# Sheet1.net
KiCad netlist of a schematic drawn in Altium Designer
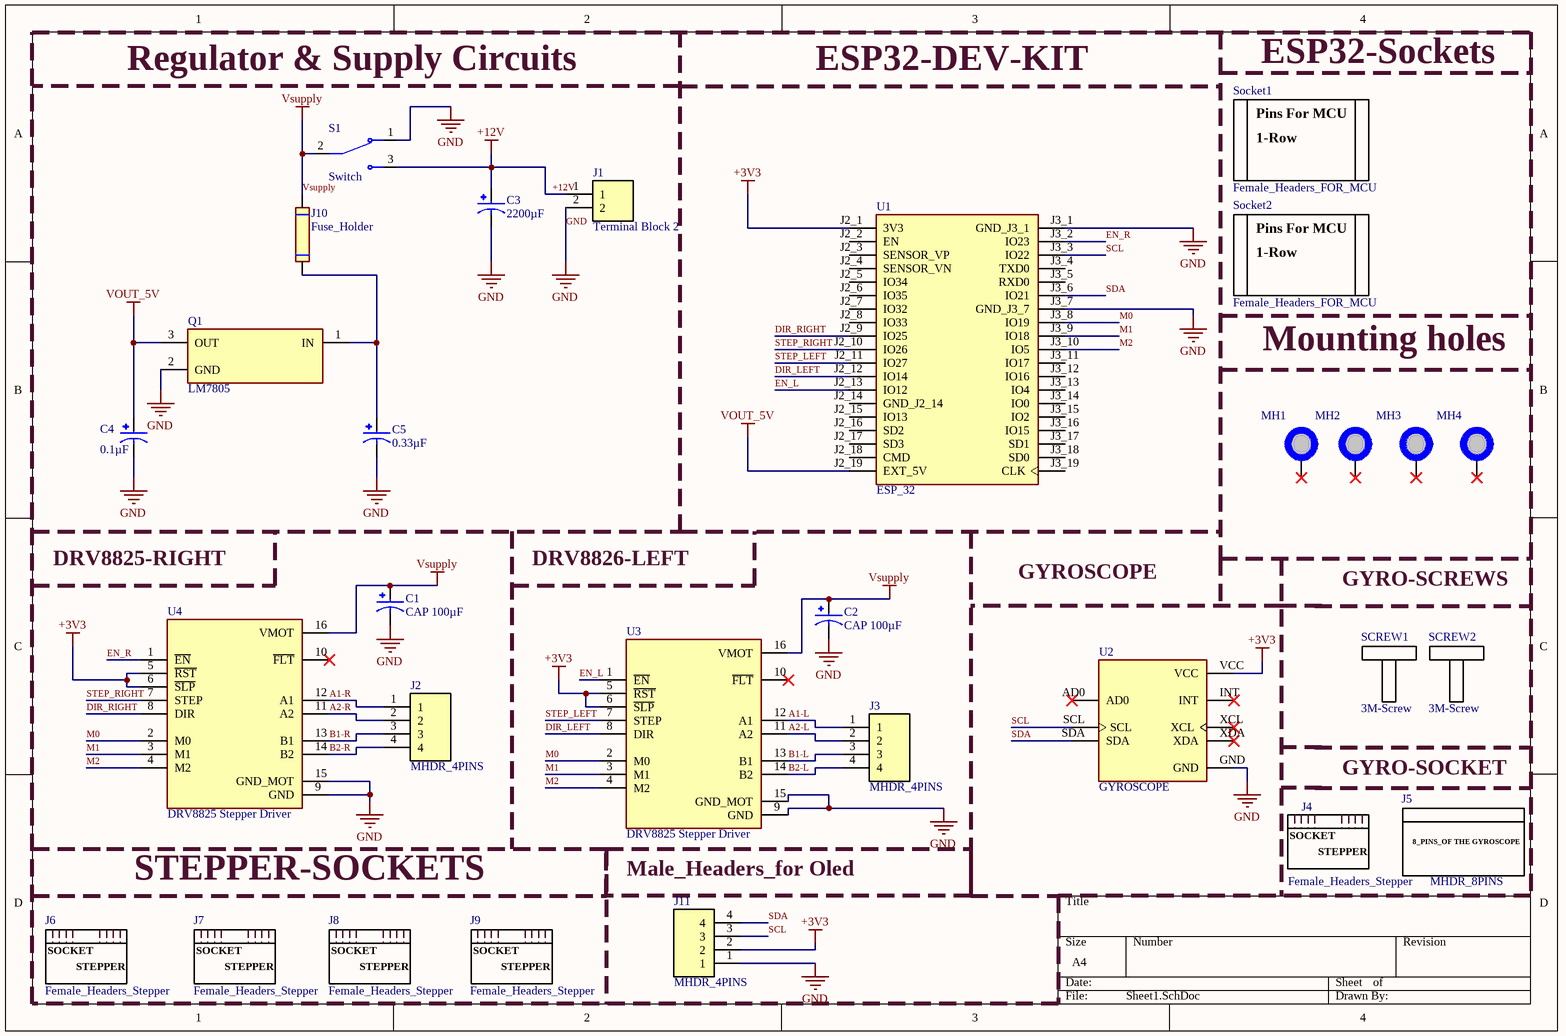
[diagram p0: Sheet1.SchDoc]

(export (version "E")
  (design (tool "Eeschema 10.0.6"))
  (components
    (comp (ref "C1") (value "CAP 100µF") (footprint "Cap_1µF") (libsource (lib "Schlib1") (part "CAP 100µF")))
    (comp (ref "C2") (value "CAP 100µF") (footprint "Cap_1µF") (libsource (lib "Schlib1") (part "CAP 100µF")))
    (comp (ref "C3")
      (value "2200µF")
      (footprint "CAP 2200UF")
      (libsource (lib "Schlib1") (part "CAP 2200µF"))
    )
    (comp (ref "C4") (value "0.1µF") (footprint "CAP 0.1UF") (libsource (lib "Schlib1") (part "CAP 0.1µF")))
    (comp (ref "C5") (value "0.33µF") (footprint "CAP 0.1UF") (libsource (lib "Schlib1") (part "CAP 0.33µF")))
    (comp (ref "J1")
      (value "Terminal Block 2")
      (footprint "Terminal Block 2")
      (libsource (lib "Schlib1") (part "Terminal Block 2"))
    )
    (comp (ref "J2") (value "MHDR_4PINS") (footprint "MHDR_4PINS") (libsource (lib "") (part "MHDR_4PINS_1")))
    (comp (ref "J3") (value "MHDR_4PINS") (footprint "MHDR_4PINS") (libsource (lib "") (part "MHDR_4PINS_1")))
    (comp (ref "J4")
      (value "Female_Headers_Stepper")
      (footprint "Female_STEPPER")
      (libsource (lib "Schlib1") (part "Female_Headers_Stepper"))
    )
    (comp (ref "J5")
      (value "MHDR_8PINS")
      (footprint "MHDR_8PINS")
      (libsource (lib "Schlib1") (part "MHDR_8PINS"))
    )
    (comp (ref "J6")
      (value "Female_Headers_Stepper")
      (footprint "Female_STEPPER")
      (libsource (lib "Schlib1") (part "Female_Headers_Stepper"))
    )
    (comp (ref "J7")
      (value "Female_Headers_Stepper")
      (footprint "Female_STEPPER")
      (libsource (lib "Schlib1") (part "Female_Headers_Stepper"))
    )
    (comp (ref "J8")
      (value "Female_Headers_Stepper")
      (footprint "Female_STEPPER")
      (libsource (lib "Schlib1") (part "Female_Headers_Stepper"))
    )
    (comp (ref "J9")
      (value "Female_Headers_Stepper")
      (footprint "Female_STEPPER")
      (libsource (lib "Schlib1") (part "Female_Headers_Stepper"))
    )
    (comp (ref "J10")
      (value "Fuse_Holder")
      (footprint "Fuse_Holder")
      (libsource (lib "Schlib1") (part "Fuse_Holder"))
    )
    (comp (ref "J11")
      (value "MHDR_4PINS")
      (footprint "MHDR_4PINS")
      (libsource (lib "Schlib1") (part "MHDR_4PINS"))
    )
    (comp (ref "MH1")
      (value "MH_7.4MMNC_3.2MMD (NO COPPER-NPTH)")
      (footprint "MH_7.4MMC_3.2MMD_NO_COPPER_NPTH")
      (libsource (lib "Schlib1") (part "MH_7.4MMNC_3.2MMD_1"))
    )
    (comp (ref "MH2")
      (value "MH_7.4MMNC_3.2MMD (NO COPPER-NPTH)")
      (footprint "MH_7.4MMC_3.2MMD_NO_COPPER_NPTH")
      (libsource (lib "Schlib1") (part "MH_7.4MMNC_3.2MMD_1"))
    )
    (comp (ref "MH3")
      (value "MH_7.4MMNC_3.2MMD (NO COPPER-NPTH)")
      (footprint "MH_7.4MMC_3.2MMD_NO_COPPER_NPTH")
      (libsource (lib "Schlib1") (part "MH_7.4MMNC_3.2MMD_1"))
    )
    (comp (ref "MH4")
      (value "MH_7.4MMNC_3.2MMD (NO COPPER-NPTH)")
      (footprint "MH_7.4MMC_3.2MMD_NO_COPPER_NPTH")
      (libsource (lib "Schlib1") (part "MH_7.4MMNC_3.2MMD_1"))
    )
    (comp (ref "Q1") (value "LM7805") (footprint "LM7805") (libsource (lib "Schlib1") (part "LM7805")))
    (comp (ref "S1") (value "Switch") (footprint "Switch") (libsource (lib "Schlib1") (part "Switch")))
    (comp (ref "SCREW1")
      (value "3M-Screw")
      (footprint "3M-SCREW")
      (libsource (lib "Schlib1") (part "3M-Screw"))
    )
    (comp (ref "SCREW2")
      (value "3M-Screw")
      (footprint "3M-SCREW")
      (libsource (lib "Schlib1") (part "3M-Screw"))
    )
    (comp (ref "Socket1")
      (value "Female_Headers_FOR_MCU")
      (footprint "Female_headers")
      (libsource (lib "Schlib1") (part "Female_Headers_FOR_MCU"))
    )
    (comp (ref "Socket2")
      (value "Female_Headers_FOR_MCU")
      (footprint "Female_headers")
      (libsource (lib "Schlib1") (part "Female_Headers_FOR_MCU"))
    )
    (comp (ref "U1") (value "ESP_32") (footprint "ESP_32") (libsource (lib "Schlib1") (part "ESP_32")))
    (comp (ref "U2")
      (value "GYROSCOPE")
      (footprint "GYROSCOPE")
      (libsource (lib "Schlib1") (part "GYROSCOPE"))
    )
    (comp (ref "U3")
      (value "DRV8825 Stepper Driver")
      (footprint "DRV8825 Stepper Driver")
      (libsource (lib "Schlib1") (part "DRV8825 Stepper Driver"))
    )
    (comp (ref "U4")
      (value "DRV8825 Stepper Driver")
      (footprint "DRV8825 Stepper Driver")
      (libsource (lib "Schlib1") (part "DRV8825 Stepper Driver"))
    )
  )
  (nets
    (net (code "1") (name "+3V3") (class "Default")
      (node (ref "J11") (pin "2") (pinfunction "2_2") (pintype "passive"))
      (node (ref "U1") (pin "J2_1") (pinfunction "3V3_J2_1") (pintype "passive"))
      (node (ref "U2") (pin "VCC") (pinfunction "VCC_VCC") (pintype "passive"))
      (node (ref "U3") (pin "5") (pinfunction "~{RST}_5") (pintype "passive"))
      (node (ref "U3") (pin "6") (pinfunction "~{SLP}_6") (pintype "passive"))
      (node (ref "U4") (pin "5") (pinfunction "~{RST}_5") (pintype "passive"))
      (node (ref "U4") (pin "6") (pinfunction "~{SLP}_6") (pintype "passive"))
    )
    (net (code "2") (name "+12V") (class "Default")
      (node (ref "C3") (pin "P") (pinfunction "P_P") (pintype "passive"))
      (node (ref "J1") (pin "1") (pinfunction "1_1") (pintype "passive"))
      (node (ref "S1") (pin "3") (pinfunction "3_3") (pintype "passive"))
    )
    (net (code "3") (name "/A1-L") (class "Default")
      (node (ref "J3") (pin "1") (pinfunction "1_1") (pintype "passive"))
      (node (ref "U3") (pin "12") (pinfunction "A1_12") (pintype "passive"))
    )
    (net (code "4") (name "/A1-R") (class "Default")
      (node (ref "J2") (pin "1") (pinfunction "1_1") (pintype "passive"))
      (node (ref "U4") (pin "12") (pinfunction "A1_12") (pintype "passive"))
    )
    (net (code "5") (name "/A2-L") (class "Default")
      (node (ref "J3") (pin "2") (pinfunction "2_2") (pintype "passive"))
      (node (ref "U3") (pin "11") (pinfunction "A2_11") (pintype "passive"))
    )
    (net (code "6") (name "/A2-R") (class "Default")
      (node (ref "J2") (pin "2") (pinfunction "2_2") (pintype "passive"))
      (node (ref "U4") (pin "11") (pinfunction "A2_11") (pintype "passive"))
    )
    (net (code "7") (name "/B1-L") (class "Default")
      (node (ref "J3") (pin "3") (pinfunction "3_3") (pintype "passive"))
      (node (ref "U3") (pin "13") (pinfunction "B1_13") (pintype "passive"))
    )
    (net (code "8") (name "/B1-R") (class "Default")
      (node (ref "J2") (pin "3") (pinfunction "3_3") (pintype "passive"))
      (node (ref "U4") (pin "13") (pinfunction "B1_13") (pintype "passive"))
    )
    (net (code "9") (name "/B2-L") (class "Default")
      (node (ref "J3") (pin "4") (pinfunction "4_4") (pintype "passive"))
      (node (ref "U3") (pin "14") (pinfunction "B2_14") (pintype "passive"))
    )
    (net (code "10") (name "/B2-R") (class "Default")
      (node (ref "J2") (pin "4") (pinfunction "4_4") (pintype "passive"))
      (node (ref "U4") (pin "14") (pinfunction "B2_14") (pintype "passive"))
    )
    (net (code "11") (name "/DIR_LEFT") (class "Default")
      (node (ref "U1") (pin "J2_12") (pinfunction "IO14_J2_12") (pintype "passive"))
      (node (ref "U3") (pin "8") (pinfunction "DIR_8") (pintype "passive"))
    )
    (net (code "12") (name "/DIR_RIGHT") (class "Default")
      (node (ref "U1") (pin "J2_9") (pinfunction "IO25_J2_9") (pintype "passive"))
      (node (ref "U4") (pin "8") (pinfunction "DIR_8") (pintype "passive"))
    )
    (net (code "13") (name "/EN_L") (class "Default")
      (node (ref "U1") (pin "J2_13") (pinfunction "IO12_J2_13") (pintype "passive"))
      (node (ref "U3") (pin "1") (pinfunction "~{EN}_1") (pintype "passive"))
    )
    (net (code "14") (name "/EN_R") (class "Default")
      (node (ref "U1") (pin "J3_2") (pinfunction "IO23_J3_2") (pintype "passive"))
      (node (ref "U4") (pin "1") (pinfunction "~{EN}_1") (pintype "passive"))
    )
    (net (code "15") (name "/M0") (class "Default")
      (node (ref "U1") (pin "J3_8") (pinfunction "IO19_J3_8") (pintype "passive"))
      (node (ref "U3") (pin "2") (pinfunction "M0_2") (pintype "passive"))
      (node (ref "U4") (pin "2") (pinfunction "M0_2") (pintype "passive"))
    )
    (net (code "16") (name "/M1") (class "Default")
      (node (ref "U1") (pin "J3_9") (pinfunction "IO18_J3_9") (pintype "passive"))
      (node (ref "U3") (pin "3") (pinfunction "M1_3") (pintype "passive"))
      (node (ref "U4") (pin "3") (pinfunction "M1_3") (pintype "passive"))
    )
    (net (code "17") (name "/M2") (class "Default")
      (node (ref "U1") (pin "J3_10") (pinfunction "IO5_J3_10") (pintype "passive"))
      (node (ref "U3") (pin "4") (pinfunction "M2_4") (pintype "passive"))
      (node (ref "U4") (pin "4") (pinfunction "M2_4") (pintype "passive"))
    )
    (net (code "18") (name "/SCL") (class "Default")
      (node (ref "J11") (pin "3") (pinfunction "3_3") (pintype "passive"))
      (node (ref "U1") (pin "J3_3") (pinfunction "IO22_J3_3") (pintype "passive"))
      (node (ref "U2") (pin "SCL") (pinfunction "SCL_SCL") (pintype "passive"))
    )
    (net (code "19") (name "/SDA") (class "Default")
      (node (ref "J11") (pin "4") (pinfunction "4_4") (pintype "passive"))
      (node (ref "U1") (pin "J3_6") (pinfunction "IO21_J3_6") (pintype "passive"))
      (node (ref "U2") (pin "SDA") (pinfunction "SDA_SDA") (pintype "passive"))
    )
    (net (code "20") (name "/STEP_LEFT") (class "Default")
      (node (ref "U1") (pin "J2_11") (pinfunction "IO27_J2_11") (pintype "passive"))
      (node (ref "U3") (pin "7") (pinfunction "STEP_7") (pintype "passive"))
    )
    (net (code "21") (name "/STEP_RIGHT") (class "Default")
      (node (ref "U1") (pin "J2_10") (pinfunction "IO26_J2_10") (pintype "passive"))
      (node (ref "U4") (pin "7") (pinfunction "STEP_7") (pintype "passive"))
    )
    (net (code "22") (name "GND") (class "Default")
      (node (ref "C1") (pin "N") (pinfunction "N_N") (pintype "passive"))
      (node (ref "C2") (pin "N") (pinfunction "N_N") (pintype "passive"))
      (node (ref "C3") (pin "N") (pinfunction "N_N") (pintype "passive"))
      (node (ref "C4") (pin "N") (pinfunction "N_N") (pintype "passive"))
      (node (ref "C5") (pin "N") (pinfunction "N_N") (pintype "passive"))
      (node (ref "J1") (pin "2") (pinfunction "2_2") (pintype "passive"))
      (node (ref "J11") (pin "1") (pinfunction "1_1") (pintype "passive"))
      (node (ref "Q1") (pin "2") (pinfunction "GND_2") (pintype "power_in"))
      (node (ref "S1") (pin "1") (pinfunction "1_1") (pintype "passive"))
      (node (ref "U1") (pin "J3_1") (pinfunction "GND_J3_1_J3_1") (pintype "passive"))
      (node (ref "U1") (pin "J3_7") (pinfunction "GND_J3_7_J3_7") (pintype "passive"))
      (node (ref "U2") (pin "GND") (pinfunction "GND_GND") (pintype "passive"))
      (node (ref "U3") (pin "15") (pinfunction "GND_MOT_15") (pintype "passive"))
      (node (ref "U3") (pin "9") (pinfunction "GND_9") (pintype "passive"))
      (node (ref "U4") (pin "15") (pinfunction "GND_MOT_15") (pintype "passive"))
      (node (ref "U4") (pin "9") (pinfunction "GND_9") (pintype "passive"))
    )
    (net (code "23") (name "Net-(Q1-IN)") (class "Default")
      (node (ref "C5") (pin "P") (pinfunction "P_P") (pintype "passive"))
      (node (ref "J10") (pin "1") (pinfunction "1_1") (pintype "passive"))
      (node (ref "Q1") (pin "1") (pinfunction "IN_1") (pintype "passive"))
    )
    (net (code "24") (name "VOUT_5V") (class "Default")
      (node (ref "C4") (pin "P") (pinfunction "P_P") (pintype "passive"))
      (node (ref "Q1") (pin "3") (pinfunction "OUT_3") (pintype "passive"))
      (node (ref "U1") (pin "J2_19") (pinfunction "EXT_5V_J2_19") (pintype "passive"))
    )
    (net (code "25") (name "Vsupply") (class "Default")
      (node (ref "C1") (pin "P") (pinfunction "P_P") (pintype "passive"))
      (node (ref "C2") (pin "P") (pinfunction "P_P") (pintype "passive"))
      (node (ref "J10") (pin "2") (pinfunction "2_2") (pintype "passive"))
      (node (ref "S1") (pin "2") (pinfunction "2_2") (pintype "passive"))
      (node (ref "U3") (pin "16") (pinfunction "VMOT_16") (pintype "passive"))
      (node (ref "U4") (pin "16") (pinfunction "VMOT_16") (pintype "passive"))
    )
    (net (code "26") (name "unconnected-(MH1-Pad1)") (class "Default")
      (node (ref "MH1") (pin "1") (pinfunction "1_1") (pintype "passive+no_connect"))
    )
    (net (code "27") (name "unconnected-(MH2-Pad1)") (class "Default")
      (node (ref "MH2") (pin "1") (pinfunction "1_1") (pintype "passive+no_connect"))
    )
    (net (code "28") (name "unconnected-(MH3-Pad1)") (class "Default")
      (node (ref "MH3") (pin "1") (pinfunction "1_1") (pintype "passive+no_connect"))
    )
    (net (code "29") (name "unconnected-(MH4-Pad1)") (class "Default")
      (node (ref "MH4") (pin "1") (pinfunction "1_1") (pintype "passive+no_connect"))
    )
    (net (code "30") (name "unconnected-(U1-CLK-PadJ3_19)") (class "Default")
      (node (ref "U1") (pin "J3_19") (pinfunction "CLK_J3_19") (pintype "passive"))
    )
    (net (code "31") (name "unconnected-(U1-CMD-PadJ2_18)") (class "Default")
      (node (ref "U1") (pin "J2_18") (pinfunction "CMD_J2_18") (pintype "passive"))
    )
    (net (code "32") (name "unconnected-(U1-EN-PadJ2_2)") (class "Default")
      (node (ref "U1") (pin "J2_2") (pinfunction "EN_J2_2") (pintype "passive"))
    )
    (net (code "33") (name "unconnected-(U1-GND_J2_14-PadJ2_14)") (class "Default")
      (node (ref "U1") (pin "J2_14") (pinfunction "GND_J2_14_J2_14") (pintype "passive"))
    )
    (net (code "34") (name "unconnected-(U1-IO0-PadJ3_14)") (class "Default")
      (node (ref "U1") (pin "J3_14") (pinfunction "IO0_J3_14") (pintype "passive"))
    )
    (net (code "35") (name "unconnected-(U1-IO2-PadJ3_15)") (class "Default")
      (node (ref "U1") (pin "J3_15") (pinfunction "IO2_J3_15") (pintype "passive"))
    )
    (net (code "36") (name "unconnected-(U1-IO4-PadJ3_13)") (class "Default")
      (node (ref "U1") (pin "J3_13") (pinfunction "IO4_J3_13") (pintype "passive"))
    )
    (net (code "37") (name "unconnected-(U1-IO13-PadJ2_15)") (class "Default")
      (node (ref "U1") (pin "J2_15") (pinfunction "IO13_J2_15") (pintype "passive"))
    )
    (net (code "38") (name "unconnected-(U1-IO15-PadJ3_16)") (class "Default")
      (node (ref "U1") (pin "J3_16") (pinfunction "IO15_J3_16") (pintype "passive"))
    )
    (net (code "39") (name "unconnected-(U1-IO16-PadJ3_12)") (class "Default")
      (node (ref "U1") (pin "J3_12") (pinfunction "IO16_J3_12") (pintype "passive"))
    )
    (net (code "40") (name "unconnected-(U1-IO17-PadJ3_11)") (class "Default")
      (node (ref "U1") (pin "J3_11") (pinfunction "IO17_J3_11") (pintype "passive"))
    )
    (net (code "41") (name "unconnected-(U1-IO32-PadJ2_7)") (class "Default")
      (node (ref "U1") (pin "J2_7") (pinfunction "IO32_J2_7") (pintype "passive"))
    )
    (net (code "42") (name "unconnected-(U1-IO33-PadJ2_8)") (class "Default")
      (node (ref "U1") (pin "J2_8") (pinfunction "IO33_J2_8") (pintype "passive"))
    )
    (net (code "43") (name "unconnected-(U1-IO34-PadJ2_5)") (class "Default")
      (node (ref "U1") (pin "J2_5") (pinfunction "IO34_J2_5") (pintype "passive"))
    )
    (net (code "44") (name "unconnected-(U1-IO35-PadJ2_6)") (class "Default")
      (node (ref "U1") (pin "J2_6") (pinfunction "IO35_J2_6") (pintype "passive"))
    )
    (net (code "45") (name "unconnected-(U1-RXD0-PadJ3_5)") (class "Default")
      (node (ref "U1") (pin "J3_5") (pinfunction "RXD0_J3_5") (pintype "passive"))
    )
    (net (code "46") (name "unconnected-(U1-SD0-PadJ3_18)") (class "Default")
      (node (ref "U1") (pin "J3_18") (pinfunction "SD0_J3_18") (pintype "passive"))
    )
    (net (code "47") (name "unconnected-(U1-SD1-PadJ3_17)") (class "Default")
      (node (ref "U1") (pin "J3_17") (pinfunction "SD1_J3_17") (pintype "passive"))
    )
    (net (code "48") (name "unconnected-(U1-SD2-PadJ2_16)") (class "Default")
      (node (ref "U1") (pin "J2_16") (pinfunction "SD2_J2_16") (pintype "passive"))
    )
    (net (code "49") (name "unconnected-(U1-SD3-PadJ2_17)") (class "Default")
      (node (ref "U1") (pin "J2_17") (pinfunction "SD3_J2_17") (pintype "passive"))
    )
    (net (code "50") (name "unconnected-(U1-SENSOR_VN-PadJ2_4)") (class "Default")
      (node (ref "U1") (pin "J2_4") (pinfunction "SENSOR_VN_J2_4") (pintype "passive"))
    )
    (net (code "51") (name "unconnected-(U1-SENSOR_VP-PadJ2_3)") (class "Default")
      (node (ref "U1") (pin "J2_3") (pinfunction "SENSOR_VP_J2_3") (pintype "passive"))
    )
    (net (code "52") (name "unconnected-(U1-TXD0-PadJ3_4)") (class "Default")
      (node (ref "U1") (pin "J3_4") (pinfunction "TXD0_J3_4") (pintype "passive"))
    )
    (net (code "53") (name "unconnected-(U2-PadAD0)") (class "Default")
      (node (ref "U2") (pin "AD0") (pinfunction "AD0_AD0") (pintype "passive+no_connect"))
    )
    (net (code "54") (name "unconnected-(U2-PadINT)") (class "Default")
      (node (ref "U2") (pin "INT") (pinfunction "INT_INT") (pintype "passive+no_connect"))
    )
    (net (code "55") (name "unconnected-(U2-PadXCL)") (class "Default")
      (node (ref "U2") (pin "XCL") (pinfunction "XCL_XCL") (pintype "passive+no_connect"))
    )
    (net (code "56") (name "unconnected-(U2-PadXDA)") (class "Default")
      (node (ref "U2") (pin "XDA") (pinfunction "XDA_XDA") (pintype "passive+no_connect"))
    )
    (net (code "57") (name "unconnected-(U3-~{FLT}-Pad10)") (class "Default")
      (node (ref "U3") (pin "10") (pinfunction "~{FLT}_10") (pintype "passive+no_connect"))
    )
    (net (code "58") (name "unconnected-(U4-~{FLT}-Pad10)") (class "Default")
      (node (ref "U4") (pin "10") (pinfunction "~{FLT}_10") (pintype "passive+no_connect"))
    )
  )
)
